# transmitter_crystal.net
KiCad netlist of a schematic drawn in EAGLE
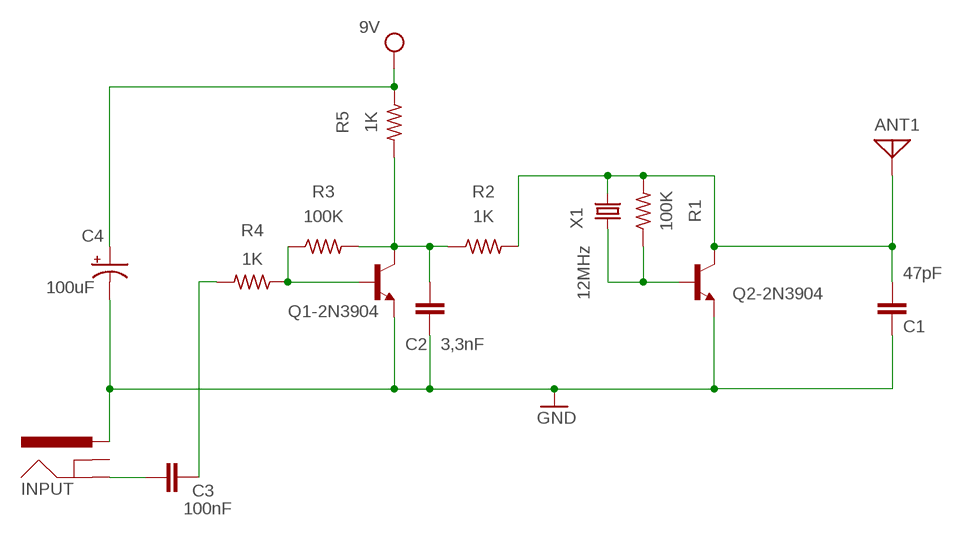
[diagram p0: schematic, sheet 1]

(export (version "E")
  (design (tool "Eeschema 10.0.6"))
  (components
    (comp (ref "ANT1")
      (value "ANTENNA")
      (footprint "eagle-import:PAD-01")
      (libsource (lib "eagle-import") (part "ANTENNA"))
    )
    (comp (ref "C1")
      (value "47pF")
      (footprint "eagle-import:XC10B6")
      (libsource (lib "eagle-import") (part "CXXC10B6"))
    )
    (comp (ref "C2")
      (value "3,3nF")
      (footprint "eagle-import:XC10B6")
      (libsource (lib "eagle-import") (part "CXXC10B6"))
    )
    (comp (ref "C3")
      (value "100nF")
      (footprint "eagle-import:XC10B6")
      (libsource (lib "eagle-import") (part "CXXC10B6"))
    )
    (comp (ref "C4")
      (value "100uF")
      (footprint "eagle-import:NIC_10X10.5_CAP")
      (libsource (lib "eagle-import") (part "100UF-POLAR-10X10.5-63V-20%"))
    )
    (comp (ref "INPUT")
      (value "POWER_JACKPTH_SMD_COMBO")
      (footprint "eagle-import:POWER_JACK_COMBO")
      (libsource (lib "eagle-import") (part "POWER_JACKPTH_SMD_COMBO"))
    )
    (comp (ref "Q1-2N3904")
      (value "200mA/40V")
      (footprint "eagle-import:TO-92")
      (libsource (lib "eagle-import") (part "TRANS_NPN-2N3904"))
    )
    (comp (ref "Q2-2N3904")
      (value "200mA/40V")
      (footprint "eagle-import:TO-92")
      (libsource (lib "eagle-import") (part "TRANS_NPN-2N3904"))
    )
    (comp (ref "R1")
      (value "100K")
      (footprint "eagle-import:RESAD724W46L381D178B")
      (libsource (lib "eagle-import") (part "R-USAXIAL-7.2MM-PITCH_"))
    )
    (comp (ref "R2")
      (value "1K")
      (footprint "eagle-import:RESAD724W46L381D178B")
      (libsource (lib "eagle-import") (part "R-USAXIAL-7.2MM-PITCH_"))
    )
    (comp (ref "R3")
      (value "100K")
      (footprint "eagle-import:RESAD724W46L381D178B")
      (libsource (lib "eagle-import") (part "R-USAXIAL-7.2MM-PITCH_"))
    )
    (comp (ref "R4")
      (value "1K")
      (footprint "eagle-import:RESAD724W46L381D178B")
      (libsource (lib "eagle-import") (part "R-USAXIAL-7.2MM-PITCH_"))
    )
    (comp (ref "R5")
      (value "1K")
      (footprint "eagle-import:RESAD724W46L381D178B")
      (libsource (lib "eagle-import") (part "R-USAXIAL-7.2MM-PITCH_"))
    )
    (comp (ref "X1")
      (value "12MHz")
      (footprint "eagle-import:86SMX")
      (libsource (lib "eagle-import") (part "CRYSTAL68SMX"))
    )
  )
  (nets
    (net (code "1") (name "GND") (class "Default")
      (node (ref "C1") (pin "2") (pinfunction "2_2") (pintype "passive"))
      (node (ref "C2") (pin "2") (pinfunction "2_2") (pintype "passive"))
      (node (ref "C4") (pin "-") (pinfunction "-_-") (pintype "passive"))
      (node (ref "INPUT") (pin "POWER") (pinfunction "PWR_POWER") (pintype "bidirectional"))
      (node (ref "Q1-2N3904") (pin "1") (pinfunction "E_1") (pintype "passive"))
      (node (ref "Q2-2N3904") (pin "1") (pinfunction "E_1") (pintype "passive"))
    )
    (net (code "2") (name "Net-(C3-Pad2)") (class "Default")
      (node (ref "C3") (pin "2") (pinfunction "2_2") (pintype "passive"))
      (node (ref "R4") (pin "2") (pinfunction "2_2") (pintype "passive"))
    )
    (net (code "3") (name "Net-(INPUT-GND)") (class "Default")
      (node (ref "C3") (pin "1") (pinfunction "1_1") (pintype "passive"))
      (node (ref "INPUT") (pin "GND@1") (pinfunction "GND_GND@1") (pintype "bidirectional"))
    )
    (net (code "4") (name "Net-(Q1-2N3904-B)") (class "Default")
      (node (ref "Q1-2N3904") (pin "2") (pinfunction "B_2") (pintype "passive"))
      (node (ref "R3") (pin "1") (pinfunction "1_1") (pintype "passive"))
      (node (ref "R4") (pin "1") (pinfunction "1_1") (pintype "passive"))
    )
    (net (code "5") (name "Net-(Q1-2N3904-C)") (class "Default")
      (node (ref "C2") (pin "1") (pinfunction "1_1") (pintype "passive"))
      (node (ref "Q1-2N3904") (pin "3") (pinfunction "C_3") (pintype "passive"))
      (node (ref "R2") (pin "1") (pinfunction "1_1") (pintype "passive"))
      (node (ref "R3") (pin "2") (pinfunction "2_2") (pintype "passive"))
      (node (ref "R5") (pin "2") (pinfunction "2_2") (pintype "passive"))
    )
    (net (code "6") (name "Net-(Q2-2N3904-B)") (class "Default")
      (node (ref "Q2-2N3904") (pin "2") (pinfunction "B_2") (pintype "passive"))
      (node (ref "R1") (pin "1") (pinfunction "1_1") (pintype "passive"))
      (node (ref "X1") (pin "1") (pinfunction "1_1") (pintype "passive"))
    )
    (net (code "7") (name "Net-(Q2-2N3904-C)") (class "Default")
      (node (ref "ANT1") (pin "1") (pinfunction "1_1") (pintype "output"))
      (node (ref "C1") (pin "1") (pinfunction "1_1") (pintype "passive"))
      (node (ref "Q2-2N3904") (pin "3") (pinfunction "C_3") (pintype "passive"))
      (node (ref "R1") (pin "2") (pinfunction "2_2") (pintype "passive"))
      (node (ref "R2") (pin "2") (pinfunction "2_2") (pintype "passive"))
      (node (ref "X1") (pin "4") (pinfunction "2_4") (pintype "passive"))
    )
    (net (code "8") (name "VCC") (class "Default")
      (node (ref "C4") (pin "+") (pinfunction "+_+") (pintype "passive"))
      (node (ref "R5") (pin "1") (pinfunction "1_1") (pintype "passive"))
    )
    (net (code "9") (name "unconnected-(INPUT-GNDBREAK-PadGND)") (class "Default")
      (node (ref "INPUT") (pin "GND") (pinfunction "GNDBREAK_GND") (pintype "bidirectional"))
    )
  )
)
